# RX.net
KiCad netlist of a schematic drawn in EAGLE
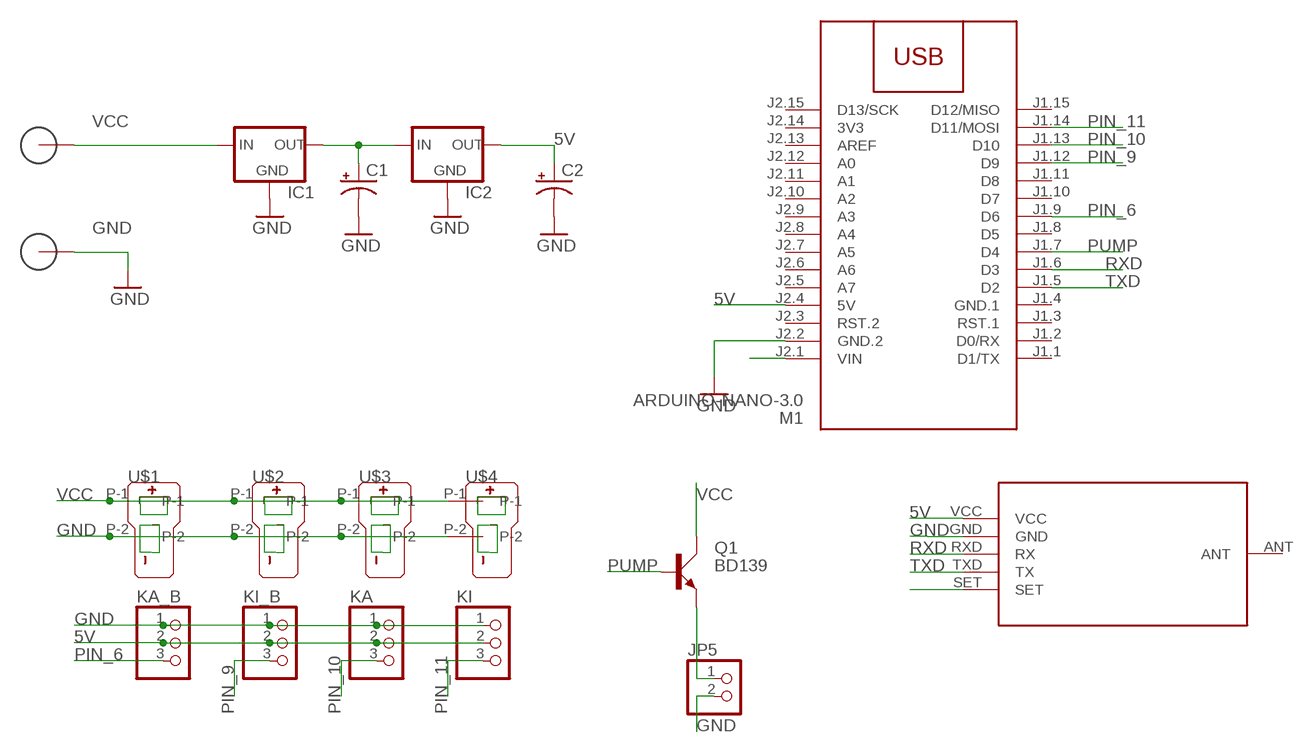
[diagram p0: schematic, sheet 1]

(export (version "E")
  (design (tool "Eeschema 10.0.6"))
  (components
    (comp (ref "C1")
      (value "CPOL-USE2.5-7")
      (footprint "eagle-import:E2,5-7")
      (libsource (lib "eagle-import") (part "CPOL-USE2.5-7"))
    )
    (comp (ref "C2")
      (value "CPOL-USE2.5-7")
      (footprint "eagle-import:E2,5-7")
      (libsource (lib "eagle-import") (part "CPOL-USE2.5-7"))
    )
    (comp (ref "H1")
      (value "3MM_HOLE")
      (footprint "eagle-import:3MM_HOLE")
      (libsource (lib "eagle-import") (part "3MM_HOLE"))
    )
    (comp (ref "H2")
      (value "3MM_HOLE")
      (footprint "eagle-import:3MM_HOLE")
      (libsource (lib "eagle-import") (part "3MM_HOLE"))
    )
    (comp (ref "IC1")
      (value "78XXS")
      (footprint "eagle-import:78XXS")
      (libsource (lib "eagle-import") (part "78XXS"))
    )
    (comp (ref "IC2")
      (value "78XXS")
      (footprint "eagle-import:78XXS")
      (libsource (lib "eagle-import") (part "78XXS"))
    )
    (comp (ref "JP5")
      (value "PINHD-1X2")
      (footprint "eagle-import:1X02")
      (libsource (lib "eagle-import") (part "PINHD-1X2"))
    )
    (comp (ref "KA")
      (value "PINHD-1X3")
      (footprint "eagle-import:1X03")
      (libsource (lib "eagle-import") (part "PINHD-1X3"))
    )
    (comp (ref "KA_B")
      (value "PINHD-1X3")
      (footprint "eagle-import:1X03")
      (libsource (lib "eagle-import") (part "PINHD-1X3"))
    )
    (comp (ref "KI")
      (value "PINHD-1X3")
      (footprint "eagle-import:1X03")
      (libsource (lib "eagle-import") (part "PINHD-1X3"))
    )
    (comp (ref "KI_B")
      (value "PINHD-1X3")
      (footprint "eagle-import:1X03")
      (libsource (lib "eagle-import") (part "PINHD-1X3"))
    )
    (comp (ref "M1")
      (value "ARDUINO-NANO-3.0")
      (footprint "eagle-import:ARDUINO-NANO-3.0")
      (libsource (lib "eagle-import") (part "ARDUINO-NANO-3.0"))
    )
    (comp (ref "Q1")
      (value "BD139")
      (footprint "eagle-import:TO126AV")
      (libsource (lib "eagle-import") (part "BD139"))
    )
    (comp (ref "U$1")
      (value "T-PLUG_CONNECTOR")
      (footprint "eagle-import:T_PLUG_CONNECTOR")
      (libsource (lib "eagle-import") (part "T-PLUG_CONNECTOR"))
    )
    (comp (ref "U$2")
      (value "T-PLUG_CONNECTOR")
      (footprint "eagle-import:T_PLUG_CONNECTOR")
      (libsource (lib "eagle-import") (part "T-PLUG_CONNECTOR"))
    )
    (comp (ref "U$3")
      (value "T-PLUG_CONNECTOR")
      (footprint "eagle-import:T_PLUG_CONNECTOR")
      (libsource (lib "eagle-import") (part "T-PLUG_CONNECTOR"))
    )
    (comp (ref "U$4")
      (value "T-PLUG_CONNECTOR")
      (footprint "eagle-import:T_PLUG_CONNECTOR")
      (libsource (lib "eagle-import") (part "T-PLUG_CONNECTOR"))
    )
    (comp (ref "U$5")
      (value "HC-12_FOOTPRINT")
      (footprint "eagle-import:HC-12_FOOTPRINT")
      (libsource (lib "eagle-import") (part "HC-12_FOOTPRINT"))
    )
  )
  (nets
    (net (code "1") (name "/3V3") (class "Default")
      (node (ref "M1") (pin "J2.14") (pinfunction "3V3_J2.14") (pintype "power_in"))
    )
    (net (code "2") (name "/5V") (class "Default")
      (node (ref "C2") (pin "+") (pinfunction "+_+") (pintype "passive"))
      (node (ref "IC2") (pin "OUT") (pinfunction "OUT_OUT") (pintype "passive"))
      (node (ref "KA") (pin "2") (pinfunction "2_2") (pintype "passive"))
      (node (ref "KA_B") (pin "2") (pinfunction "2_2") (pintype "passive"))
      (node (ref "KI") (pin "2") (pinfunction "2_2") (pintype "passive"))
      (node (ref "KI_B") (pin "2") (pinfunction "2_2") (pintype "passive"))
      (node (ref "M1") (pin "J2.4") (pinfunction "5V_J2.4") (pintype "power_in"))
      (node (ref "U$5") (pin "VCC") (pinfunction "VCC_VCC") (pintype "bidirectional"))
    )
    (net (code "3") (name "/GND.1") (class "Default")
      (node (ref "M1") (pin "J1.4") (pinfunction "GND.1_J1.4") (pintype "power_in"))
    )
    (net (code "4") (name "/PIN_6") (class "Default")
      (node (ref "KA_B") (pin "3") (pinfunction "3_3") (pintype "passive"))
      (node (ref "M1") (pin "J1.9") (pinfunction "D6_J1.9") (pintype "bidirectional"))
    )
    (net (code "5") (name "/PIN_9") (class "Default")
      (node (ref "KI_B") (pin "3") (pinfunction "3_3") (pintype "passive"))
      (node (ref "M1") (pin "J1.12") (pinfunction "D9_J1.12") (pintype "bidirectional"))
    )
    (net (code "6") (name "/PIN_10") (class "Default")
      (node (ref "KA") (pin "3") (pinfunction "3_3") (pintype "passive"))
      (node (ref "M1") (pin "J1.13") (pinfunction "D10_J1.13") (pintype "bidirectional"))
    )
    (net (code "7") (name "/PIN_11") (class "Default")
      (node (ref "KI") (pin "3") (pinfunction "3_3") (pintype "passive"))
      (node (ref "M1") (pin "J1.14") (pinfunction "D11/MOSI_J1.14") (pintype "bidirectional"))
    )
    (net (code "8") (name "/PUMP") (class "Default")
      (node (ref "M1") (pin "J1.7") (pinfunction "D4_J1.7") (pintype "bidirectional"))
      (node (ref "Q1") (pin "B") (pinfunction "B_B") (pintype "passive"))
    )
    (net (code "9") (name "/RXD") (class "Default")
      (node (ref "M1") (pin "J1.6") (pinfunction "D3_J1.6") (pintype "bidirectional"))
      (node (ref "U$5") (pin "RXD") (pinfunction "RX_RXD") (pintype "bidirectional"))
    )
    (net (code "10") (name "/TXD") (class "Default")
      (node (ref "M1") (pin "J1.5") (pinfunction "D2_J1.5") (pintype "bidirectional"))
      (node (ref "U$5") (pin "TXD") (pinfunction "TX_TXD") (pintype "bidirectional"))
    )
    (net (code "11") (name "/VCC") (class "Default")
      (node (ref "H1") (pin "P$1") (pinfunction "GND_P$1") (pintype "bidirectional"))
      (node (ref "H1") (pin "P$2") (pinfunction "GND_P$2") (pintype "bidirectional"))
      (node (ref "H1") (pin "P$3") (pinfunction "GND_P$3") (pintype "bidirectional"))
      (node (ref "H1") (pin "P$4") (pinfunction "GND_P$4") (pintype "bidirectional"))
      (node (ref "H1") (pin "P$5") (pinfunction "GND_P$5") (pintype "bidirectional"))
      (node (ref "H1") (pin "P$6") (pinfunction "GND_P$6") (pintype "bidirectional"))
      (node (ref "H1") (pin "P$7") (pinfunction "GND_P$7") (pintype "bidirectional"))
      (node (ref "H1") (pin "P$8") (pinfunction "GND_P$8") (pintype "bidirectional"))
      (node (ref "H1") (pin "P$9") (pinfunction "GND_P$9") (pintype "bidirectional"))
      (node (ref "IC1") (pin "IN") (pinfunction "IN_IN") (pintype "input"))
      (node (ref "Q1") (pin "C") (pinfunction "C_C") (pintype "passive"))
      (node (ref "U$1") (pin "P-1") (pinfunction "P-1_P-1") (pintype "passive"))
      (node (ref "U$2") (pin "P-1") (pinfunction "P-1_P-1") (pintype "passive"))
      (node (ref "U$3") (pin "P-1") (pinfunction "P-1_P-1") (pintype "passive"))
      (node (ref "U$4") (pin "P-1") (pinfunction "P-1_P-1") (pintype "passive"))
    )
    (net (code "12") (name "GND") (class "Default")
      (node (ref "C1") (pin "-") (pinfunction "-_-") (pintype "passive"))
      (node (ref "C2") (pin "-") (pinfunction "-_-") (pintype "passive"))
      (node (ref "H2") (pin "P$1") (pinfunction "GND_P$1") (pintype "bidirectional"))
      (node (ref "H2") (pin "P$2") (pinfunction "GND_P$2") (pintype "bidirectional"))
      (node (ref "H2") (pin "P$3") (pinfunction "GND_P$3") (pintype "bidirectional"))
      (node (ref "H2") (pin "P$4") (pinfunction "GND_P$4") (pintype "bidirectional"))
      (node (ref "H2") (pin "P$5") (pinfunction "GND_P$5") (pintype "bidirectional"))
      (node (ref "H2") (pin "P$6") (pinfunction "GND_P$6") (pintype "bidirectional"))
      (node (ref "H2") (pin "P$7") (pinfunction "GND_P$7") (pintype "bidirectional"))
      (node (ref "H2") (pin "P$8") (pinfunction "GND_P$8") (pintype "bidirectional"))
      (node (ref "H2") (pin "P$9") (pinfunction "GND_P$9") (pintype "bidirectional"))
      (node (ref "IC1") (pin "GND") (pinfunction "GND_GND") (pintype "input"))
      (node (ref "IC2") (pin "GND") (pinfunction "GND_GND") (pintype "input"))
      (node (ref "JP5") (pin "2") (pinfunction "2_2") (pintype "passive"))
      (node (ref "KA") (pin "1") (pinfunction "1_1") (pintype "passive"))
      (node (ref "KA_B") (pin "1") (pinfunction "1_1") (pintype "passive"))
      (node (ref "KI") (pin "1") (pinfunction "1_1") (pintype "passive"))
      (node (ref "KI_B") (pin "1") (pinfunction "1_1") (pintype "passive"))
      (node (ref "M1") (pin "J2.2") (pinfunction "GND.2_J2.2") (pintype "power_in"))
      (node (ref "U$1") (pin "P-2") (pinfunction "P-2_P-2") (pintype "passive"))
      (node (ref "U$2") (pin "P-2") (pinfunction "P-2_P-2") (pintype "passive"))
      (node (ref "U$3") (pin "P-2") (pinfunction "P-2_P-2") (pintype "passive"))
      (node (ref "U$4") (pin "P-2") (pinfunction "P-2_P-2") (pintype "passive"))
      (node (ref "U$5") (pin "GND") (pinfunction "GND_GND") (pintype "bidirectional"))
    )
    (net (code "13") (name "Net-(C1-Pad+)") (class "Default")
      (node (ref "C1") (pin "+") (pinfunction "+_+") (pintype "passive"))
      (node (ref "IC1") (pin "OUT") (pinfunction "OUT_OUT") (pintype "passive"))
      (node (ref "IC2") (pin "IN") (pinfunction "IN_IN") (pintype "input"))
    )
    (net (code "14") (name "Net-(JP5-Pad1)") (class "Default")
      (node (ref "JP5") (pin "1") (pinfunction "1_1") (pintype "passive"))
      (node (ref "Q1") (pin "E") (pinfunction "E_E") (pintype "passive"))
    )
    (net (code "15") (name "unconnected-(M1-A0-PadJ2.12)") (class "Default")
      (node (ref "M1") (pin "J2.12") (pinfunction "A0_J2.12") (pintype "bidirectional"))
    )
    (net (code "16") (name "unconnected-(M1-A1-PadJ2.11)") (class "Default")
      (node (ref "M1") (pin "J2.11") (pinfunction "A1_J2.11") (pintype "bidirectional"))
    )
    (net (code "17") (name "unconnected-(M1-A2-PadJ2.10)") (class "Default")
      (node (ref "M1") (pin "J2.10") (pinfunction "A2_J2.10") (pintype "bidirectional"))
    )
    (net (code "18") (name "unconnected-(M1-A3-PadJ2.9)") (class "Default")
      (node (ref "M1") (pin "J2.9") (pinfunction "A3_J2.9") (pintype "bidirectional"))
    )
    (net (code "19") (name "unconnected-(M1-A4-PadJ2.8)") (class "Default")
      (node (ref "M1") (pin "J2.8") (pinfunction "A4_J2.8") (pintype "bidirectional"))
    )
    (net (code "20") (name "unconnected-(M1-A5-PadJ2.7)") (class "Default")
      (node (ref "M1") (pin "J2.7") (pinfunction "A5_J2.7") (pintype "bidirectional"))
    )
    (net (code "21") (name "unconnected-(M1-A6-PadJ2.6)") (class "Default")
      (node (ref "M1") (pin "J2.6") (pinfunction "A6_J2.6") (pintype "bidirectional"))
    )
    (net (code "22") (name "unconnected-(M1-A7-PadJ2.5)") (class "Default")
      (node (ref "M1") (pin "J2.5") (pinfunction "A7_J2.5") (pintype "bidirectional"))
    )
    (net (code "23") (name "unconnected-(M1-AREF-PadJ2.13)") (class "Default")
      (node (ref "M1") (pin "J2.13") (pinfunction "AREF_J2.13") (pintype "bidirectional"))
    )
    (net (code "24") (name "unconnected-(M1-D0{slash}RX-PadJ1.2)") (class "Default")
      (node (ref "M1") (pin "J1.2") (pinfunction "D0/RX_J1.2") (pintype "bidirectional"))
    )
    (net (code "25") (name "unconnected-(M1-D1{slash}TX-PadJ1.1)") (class "Default")
      (node (ref "M1") (pin "J1.1") (pinfunction "D1/TX_J1.1") (pintype "bidirectional"))
    )
    (net (code "26") (name "unconnected-(M1-D5-PadJ1.8)") (class "Default")
      (node (ref "M1") (pin "J1.8") (pinfunction "D5_J1.8") (pintype "bidirectional"))
    )
    (net (code "27") (name "unconnected-(M1-D7-PadJ1.10)") (class "Default")
      (node (ref "M1") (pin "J1.10") (pinfunction "D7_J1.10") (pintype "bidirectional"))
    )
    (net (code "28") (name "unconnected-(M1-D8-PadJ1.11)") (class "Default")
      (node (ref "M1") (pin "J1.11") (pinfunction "D8_J1.11") (pintype "bidirectional"))
    )
    (net (code "29") (name "unconnected-(M1-D12{slash}MISO-PadJ1.15)") (class "Default")
      (node (ref "M1") (pin "J1.15") (pinfunction "D12/MISO_J1.15") (pintype "bidirectional"))
    )
    (net (code "30") (name "unconnected-(M1-D13{slash}SCK-PadJ2.15)") (class "Default")
      (node (ref "M1") (pin "J2.15") (pinfunction "D13/SCK_J2.15") (pintype "bidirectional"))
    )
    (net (code "31") (name "unconnected-(M1-RST.1-PadJ1.3)") (class "Default")
      (node (ref "M1") (pin "J1.3") (pinfunction "RST.1_J1.3") (pintype "bidirectional"))
    )
    (net (code "32") (name "unconnected-(M1-RST.2-PadJ2.3)") (class "Default")
      (node (ref "M1") (pin "J2.3") (pinfunction "RST.2_J2.3") (pintype "bidirectional"))
    )
    (net (code "33") (name "unconnected-(M1-VIN-PadJ2.1)") (class "Default")
      (node (ref "M1") (pin "J2.1") (pinfunction "VIN_J2.1") (pintype "power_in"))
    )
    (net (code "34") (name "unconnected-(U$5-PadANT)") (class "Default")
      (node (ref "U$5") (pin "ANT") (pinfunction "ANT_ANT") (pintype "bidirectional"))
    )
    (net (code "35") (name "unconnected-(U$5-PadSET)") (class "Default")
      (node (ref "U$5") (pin "SET") (pinfunction "SET_SET") (pintype "bidirectional"))
    )
  )
)
